# Equemetico.net
KiCad netlist of a schematic drawn in EAGLE
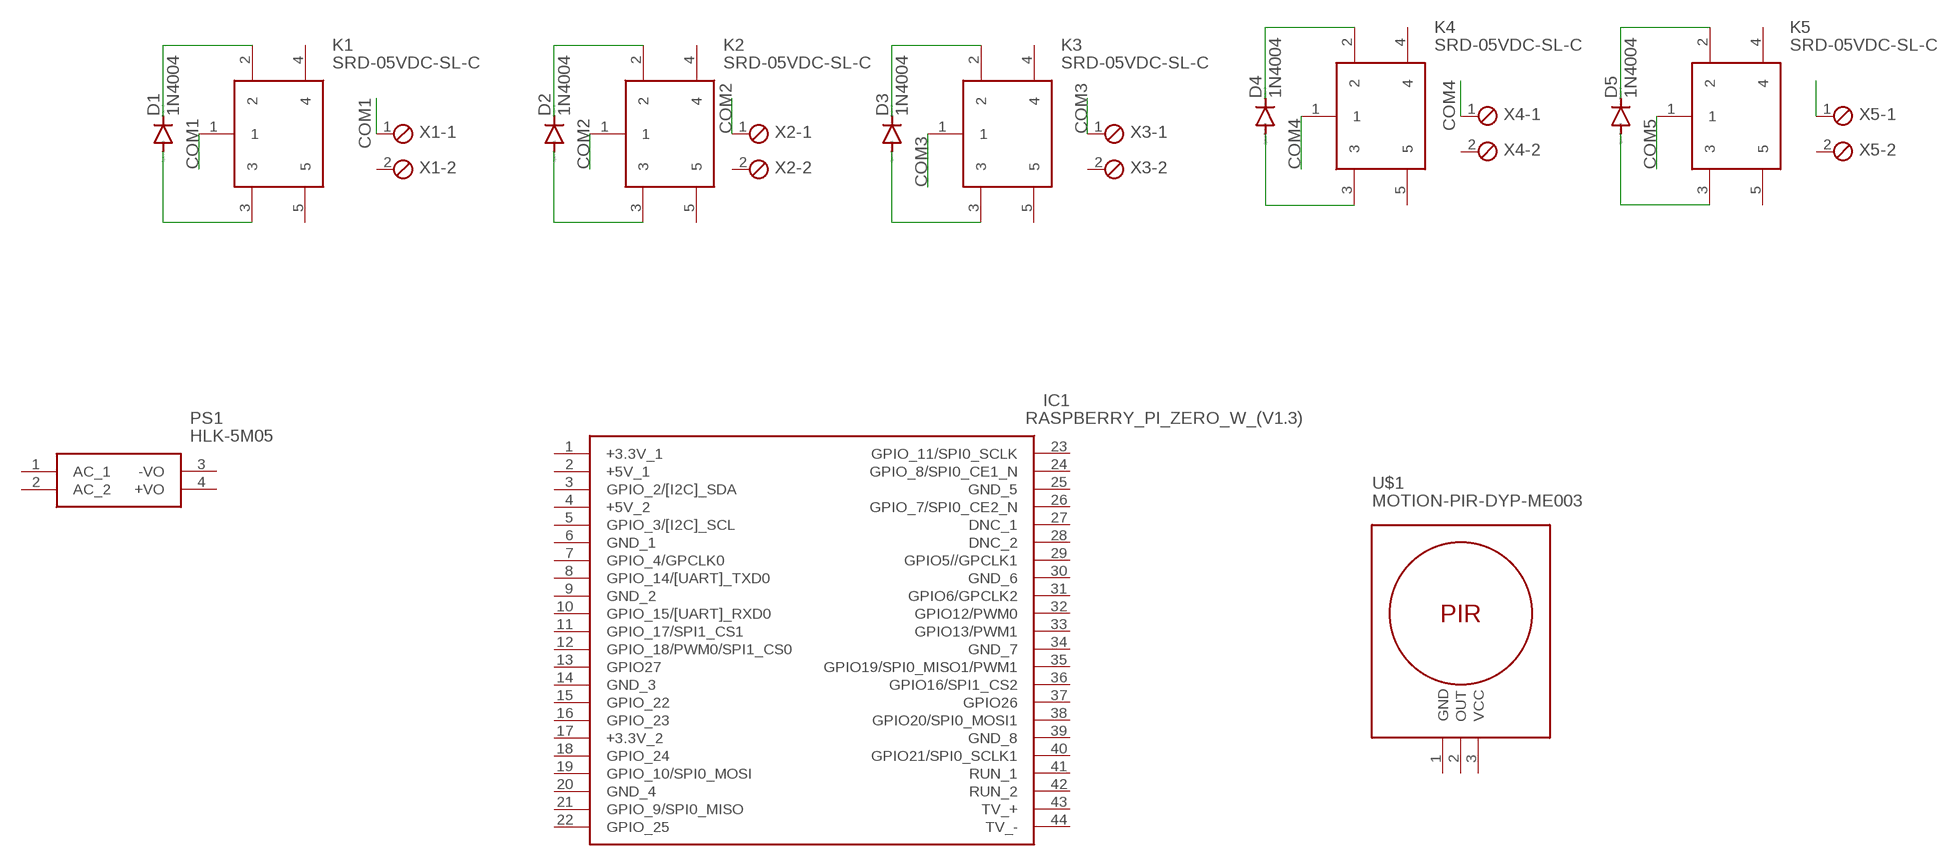
[diagram p0: schematic, sheet 1]

(export (version "E")
  (design (tool "Eeschema 10.0.6"))
  (components
    (comp (ref "D1")
      (value "1N4004")
      (footprint "eagle-import:DO41-10")
      (libsource (lib "eagle-import") (part "1N4004"))
    )
    (comp (ref "D2")
      (value "1N4004")
      (footprint "eagle-import:DO41-10")
      (libsource (lib "eagle-import") (part "1N4004"))
    )
    (comp (ref "D3")
      (value "1N4004")
      (footprint "eagle-import:DO41-10")
      (libsource (lib "eagle-import") (part "1N4004"))
    )
    (comp (ref "D4")
      (value "1N4004")
      (footprint "eagle-import:DO41-10")
      (libsource (lib "eagle-import") (part "1N4004"))
    )
    (comp (ref "D5")
      (value "1N4004")
      (footprint "eagle-import:DO41-10")
      (libsource (lib "eagle-import") (part "1N4004"))
    )
    (comp (ref "IC1")
      (value "RASPBERRY_PI_ZERO_W_(V1.3)")
      (footprint "eagle-import:RASPBERRYPIZEROWV13")
      (fields (field (name "MANUFACTURER_PART_NUMBER") "Raspberry Pi Zero W (v1.3)"))
      (libsource (lib "eagle-import") (part "RASPBERRY_PI_ZERO_W_(V1.3)"))
    )
    (comp (ref "K1")
      (value "SRD-05VDC-SL-C")
      (footprint "eagle-import:SRD")
      (libsource (lib "eagle-import") (part "SRD-05VDC-SL-C"))
    )
    (comp (ref "K2")
      (value "SRD-05VDC-SL-C")
      (footprint "eagle-import:SRD")
      (libsource (lib "eagle-import") (part "SRD-05VDC-SL-C"))
    )
    (comp (ref "K3")
      (value "SRD-05VDC-SL-C")
      (footprint "eagle-import:SRD")
      (libsource (lib "eagle-import") (part "SRD-05VDC-SL-C"))
    )
    (comp (ref "K4")
      (value "SRD-05VDC-SL-C")
      (footprint "eagle-import:SRD")
      (libsource (lib "eagle-import") (part "SRD-05VDC-SL-C"))
    )
    (comp (ref "K5")
      (value "SRD-05VDC-SL-C")
      (footprint "eagle-import:SRD")
      (libsource (lib "eagle-import") (part "SRD-05VDC-SL-C"))
    )
    (comp (ref "PS1")
      (value "HLK-5M05")
      (footprint "eagle-import:HLK5M05")
      (libsource (lib "eagle-import") (part "HLK-5M05"))
    )
    (comp (ref "U$1")
      (value "MOTION-PIR-DYP-ME003")
      (footprint "eagle-import:MOTION-PIR-DYP-ME003")
      (libsource (lib "eagle-import") (part "MOTION-PIR-DYP-ME003"))
    )
    (comp (ref "X1")
      (value "MPT2")
      (footprint "eagle-import:2POL254")
      (libsource (lib "eagle-import") (part "MPT2"))
    )
    (comp (ref "X2")
      (value "MPT2")
      (footprint "eagle-import:2POL254")
      (libsource (lib "eagle-import") (part "MPT2"))
    )
    (comp (ref "X3")
      (value "MPT2")
      (footprint "eagle-import:2POL254")
      (libsource (lib "eagle-import") (part "MPT2"))
    )
    (comp (ref "X4")
      (value "MPT2")
      (footprint "eagle-import:2POL254")
      (libsource (lib "eagle-import") (part "MPT2"))
    )
    (comp (ref "X5")
      (value "MPT2")
      (footprint "eagle-import:2POL254")
      (libsource (lib "eagle-import") (part "MPT2"))
    )
  )
  (nets
    (net (code "1") (name "/COM1") (class "Default")
      (node (ref "K1") (pin "1") (pinfunction "1_1") (pintype "bidirectional"))
      (node (ref "X1") (pin "1") (pinfunction "1_1") (pintype "passive"))
    )
    (net (code "2") (name "/COM2") (class "Default")
      (node (ref "K2") (pin "1") (pinfunction "1_1") (pintype "bidirectional"))
      (node (ref "X2") (pin "1") (pinfunction "1_1") (pintype "passive"))
    )
    (net (code "3") (name "/COM3") (class "Default")
      (node (ref "K3") (pin "1") (pinfunction "1_1") (pintype "bidirectional"))
      (node (ref "X3") (pin "1") (pinfunction "1_1") (pintype "passive"))
    )
    (net (code "4") (name "/COM4") (class "Default")
      (node (ref "K4") (pin "1") (pinfunction "1_1") (pintype "bidirectional"))
      (node (ref "X4") (pin "1") (pinfunction "1_1") (pintype "passive"))
    )
    (net (code "5") (name "/COM5") (class "Default")
      (node (ref "K5") (pin "1") (pinfunction "1_1") (pintype "bidirectional"))
      (node (ref "X5") (pin "1") (pinfunction "1_1") (pintype "passive"))
    )
    (net (code "6") (name "/GND") (class "Default")
      (node (ref "U$1") (pin "1") (pinfunction "GND_1") (pintype "power_in"))
    )
    (net (code "7") (name "/VCC") (class "Default")
      (node (ref "U$1") (pin "3") (pinfunction "VCC_3") (pintype "power_in"))
    )
    (net (code "8") (name "Net-(D1-PadA)") (class "Default")
      (node (ref "D1") (pin "A") (pinfunction "A_A") (pintype "passive"))
      (node (ref "K1") (pin "3") (pinfunction "3_3") (pintype "bidirectional"))
    )
    (net (code "9") (name "Net-(D1-PadC)") (class "Default")
      (node (ref "D1") (pin "C") (pinfunction "C_C") (pintype "passive"))
      (node (ref "K1") (pin "2") (pinfunction "2_2") (pintype "bidirectional"))
    )
    (net (code "10") (name "Net-(D2-PadA)") (class "Default")
      (node (ref "D2") (pin "A") (pinfunction "A_A") (pintype "passive"))
      (node (ref "K2") (pin "3") (pinfunction "3_3") (pintype "bidirectional"))
    )
    (net (code "11") (name "Net-(D2-PadC)") (class "Default")
      (node (ref "D2") (pin "C") (pinfunction "C_C") (pintype "passive"))
      (node (ref "K2") (pin "2") (pinfunction "2_2") (pintype "bidirectional"))
    )
    (net (code "12") (name "Net-(D3-PadA)") (class "Default")
      (node (ref "D3") (pin "A") (pinfunction "A_A") (pintype "passive"))
      (node (ref "K3") (pin "3") (pinfunction "3_3") (pintype "bidirectional"))
    )
    (net (code "13") (name "Net-(D3-PadC)") (class "Default")
      (node (ref "D3") (pin "C") (pinfunction "C_C") (pintype "passive"))
      (node (ref "K3") (pin "2") (pinfunction "2_2") (pintype "bidirectional"))
    )
    (net (code "14") (name "Net-(D4-PadA)") (class "Default")
      (node (ref "D4") (pin "A") (pinfunction "A_A") (pintype "passive"))
      (node (ref "K4") (pin "3") (pinfunction "3_3") (pintype "bidirectional"))
    )
    (net (code "15") (name "Net-(D4-PadC)") (class "Default")
      (node (ref "D4") (pin "C") (pinfunction "C_C") (pintype "passive"))
      (node (ref "K4") (pin "2") (pinfunction "2_2") (pintype "bidirectional"))
    )
    (net (code "16") (name "Net-(D5-PadA)") (class "Default")
      (node (ref "D5") (pin "A") (pinfunction "A_A") (pintype "passive"))
      (node (ref "K5") (pin "3") (pinfunction "3_3") (pintype "bidirectional"))
    )
    (net (code "17") (name "Net-(D5-PadC)") (class "Default")
      (node (ref "D5") (pin "C") (pinfunction "C_C") (pintype "passive"))
      (node (ref "K5") (pin "2") (pinfunction "2_2") (pintype "bidirectional"))
    )
    (net (code "18") (name "unconnected-(IC1-+3.3V_1-Pad1)") (class "Default")
      (node (ref "IC1") (pin "1") (pinfunction "+3.3V_1_1") (pintype "bidirectional"))
    )
    (net (code "19") (name "unconnected-(IC1-+3.3V_2-Pad17)") (class "Default")
      (node (ref "IC1") (pin "17") (pinfunction "+3.3V_2_17") (pintype "bidirectional"))
    )
    (net (code "20") (name "unconnected-(IC1-+5V_1-Pad2)") (class "Default")
      (node (ref "IC1") (pin "2") (pinfunction "+5V_1_2") (pintype "bidirectional"))
    )
    (net (code "21") (name "unconnected-(IC1-+5V_2-Pad4)") (class "Default")
      (node (ref "IC1") (pin "4") (pinfunction "+5V_2_4") (pintype "bidirectional"))
    )
    (net (code "22") (name "unconnected-(IC1-DNC_1-Pad27)") (class "Default")
      (node (ref "IC1") (pin "27") (pinfunction "DNC_1_27") (pintype "bidirectional"))
    )
    (net (code "23") (name "unconnected-(IC1-DNC_2-Pad28)") (class "Default")
      (node (ref "IC1") (pin "28") (pinfunction "DNC_2_28") (pintype "bidirectional"))
    )
    (net (code "24") (name "unconnected-(IC1-GND_1-Pad6)") (class "Default")
      (node (ref "IC1") (pin "6") (pinfunction "GND_1_6") (pintype "bidirectional"))
    )
    (net (code "25") (name "unconnected-(IC1-GND_2-Pad9)") (class "Default")
      (node (ref "IC1") (pin "9") (pinfunction "GND_2_9") (pintype "bidirectional"))
    )
    (net (code "26") (name "unconnected-(IC1-GND_3-Pad14)") (class "Default")
      (node (ref "IC1") (pin "14") (pinfunction "GND_3_14") (pintype "bidirectional"))
    )
    (net (code "27") (name "unconnected-(IC1-GND_4-Pad20)") (class "Default")
      (node (ref "IC1") (pin "20") (pinfunction "GND_4_20") (pintype "bidirectional"))
    )
    (net (code "28") (name "unconnected-(IC1-GND_5-Pad25)") (class "Default")
      (node (ref "IC1") (pin "25") (pinfunction "GND_5_25") (pintype "bidirectional"))
    )
    (net (code "29") (name "unconnected-(IC1-GND_6-Pad30)") (class "Default")
      (node (ref "IC1") (pin "30") (pinfunction "GND_6_30") (pintype "bidirectional"))
    )
    (net (code "30") (name "unconnected-(IC1-GND_7-Pad34)") (class "Default")
      (node (ref "IC1") (pin "34") (pinfunction "GND_7_34") (pintype "bidirectional"))
    )
    (net (code "31") (name "unconnected-(IC1-GND_8-Pad39)") (class "Default")
      (node (ref "IC1") (pin "39") (pinfunction "GND_8_39") (pintype "bidirectional"))
    )
    (net (code "32") (name "unconnected-(IC1-GPIO5{slash}{slash}GPCLK1-Pad29)") (class "Default")
      (node (ref "IC1") (pin "29") (pinfunction "GPIO5//GPCLK1_29") (pintype "bidirectional"))
    )
    (net (code "33") (name "unconnected-(IC1-GPIO6{slash}GPCLK2-Pad31)") (class "Default")
      (node (ref "IC1") (pin "31") (pinfunction "GPIO6/GPCLK2_31") (pintype "bidirectional"))
    )
    (net (code "34") (name "unconnected-(IC1-GPIO12{slash}PWM0-Pad32)") (class "Default")
      (node (ref "IC1") (pin "32") (pinfunction "GPIO12/PWM0_32") (pintype "bidirectional"))
    )
    (net (code "35") (name "unconnected-(IC1-GPIO13{slash}PWM1-Pad33)") (class "Default")
      (node (ref "IC1") (pin "33") (pinfunction "GPIO13/PWM1_33") (pintype "bidirectional"))
    )
    (net (code "36") (name "unconnected-(IC1-GPIO16{slash}SPI1_CS2-Pad36)") (class "Default")
      (node (ref "IC1") (pin "36") (pinfunction "GPIO16/SPI1_CS2_36") (pintype "bidirectional"))
    )
    (net (code "37") (name "unconnected-(IC1-GPIO19{slash}SPI0_MISO1{slash}PWM1-Pad35)") (class "Default")
      (node (ref "IC1") (pin "35") (pinfunction "GPIO19/SPI0_MISO1/PWM1_35") (pintype "bidirectional"))
    )
    (net (code "38") (name "unconnected-(IC1-GPIO20{slash}SPI0_MOSI1-Pad38)") (class "Default")
      (node (ref "IC1") (pin "38") (pinfunction "GPIO20/SPI0_MOSI1_38") (pintype "bidirectional"))
    )
    (net (code "39") (name "unconnected-(IC1-GPIO21{slash}SPI0_SCLK1-Pad40)") (class "Default")
      (node (ref "IC1") (pin "40") (pinfunction "GPIO21/SPI0_SCLK1_40") (pintype "bidirectional"))
    )
    (net (code "40") (name "unconnected-(IC1-GPIO26-Pad37)") (class "Default")
      (node (ref "IC1") (pin "37") (pinfunction "GPIO26_37") (pintype "bidirectional"))
    )
    (net (code "41") (name "unconnected-(IC1-GPIO27-Pad13)") (class "Default")
      (node (ref "IC1") (pin "13") (pinfunction "GPIO27_13") (pintype "bidirectional"))
    )
    (net (code "42") (name "unconnected-(IC1-GPIO_2{slash}[I2C]_SDA-Pad3)") (class "Default")
      (node (ref "IC1") (pin "3") (pinfunction "GPIO_2/[I2C]_SDA_3") (pintype "bidirectional"))
    )
    (net (code "43") (name "unconnected-(IC1-GPIO_3{slash}[I2C]_SCL-Pad5)") (class "Default")
      (node (ref "IC1") (pin "5") (pinfunction "GPIO_3/[I2C]_SCL_5") (pintype "bidirectional"))
    )
    (net (code "44") (name "unconnected-(IC1-GPIO_4{slash}GPCLK0-Pad7)") (class "Default")
      (node (ref "IC1") (pin "7") (pinfunction "GPIO_4/GPCLK0_7") (pintype "bidirectional"))
    )
    (net (code "45") (name "unconnected-(IC1-GPIO_7{slash}SPI0_CE2_N-Pad26)") (class "Default")
      (node (ref "IC1") (pin "26") (pinfunction "GPIO_7/SPI0_CE2_N_26") (pintype "bidirectional"))
    )
    (net (code "46") (name "unconnected-(IC1-GPIO_8{slash}SPI0_CE1_N-Pad24)") (class "Default")
      (node (ref "IC1") (pin "24") (pinfunction "GPIO_8/SPI0_CE1_N_24") (pintype "bidirectional"))
    )
    (net (code "47") (name "unconnected-(IC1-GPIO_9{slash}SPI0_MISO-Pad21)") (class "Default")
      (node (ref "IC1") (pin "21") (pinfunction "GPIO_9/SPI0_MISO_21") (pintype "bidirectional"))
    )
    (net (code "48") (name "unconnected-(IC1-GPIO_10{slash}SPI0_MOSI-Pad19)") (class "Default")
      (node (ref "IC1") (pin "19") (pinfunction "GPIO_10/SPI0_MOSI_19") (pintype "bidirectional"))
    )
    (net (code "49") (name "unconnected-(IC1-GPIO_11{slash}SPI0_SCLK-Pad23)") (class "Default")
      (node (ref "IC1") (pin "23") (pinfunction "GPIO_11/SPI0_SCLK_23") (pintype "bidirectional"))
    )
    (net (code "50") (name "unconnected-(IC1-GPIO_14{slash}[UART]_TXD0-Pad8)") (class "Default")
      (node (ref "IC1") (pin "8") (pinfunction "GPIO_14/[UART]_TXD0_8") (pintype "bidirectional"))
    )
    (net (code "51") (name "unconnected-(IC1-GPIO_15{slash}[UART]_RXD0-Pad10)") (class "Default")
      (node (ref "IC1") (pin "10") (pinfunction "GPIO_15/[UART]_RXD0_10") (pintype "bidirectional"))
    )
    (net (code "52") (name "unconnected-(IC1-GPIO_17{slash}SPI1_CS1-Pad11)") (class "Default")
      (node (ref "IC1") (pin "11") (pinfunction "GPIO_17/SPI1_CS1_11") (pintype "bidirectional"))
    )
    (net (code "53") (name "unconnected-(IC1-GPIO_18{slash}PWM0{slash}SPI1_CS0-Pad12)") (class "Default")
      (node (ref "IC1") (pin "12") (pinfunction "GPIO_18/PWM0/SPI1_CS0_12") (pintype "bidirectional"))
    )
    (net (code "54") (name "unconnected-(IC1-GPIO_22-Pad15)") (class "Default")
      (node (ref "IC1") (pin "15") (pinfunction "GPIO_22_15") (pintype "bidirectional"))
    )
    (net (code "55") (name "unconnected-(IC1-GPIO_23-Pad16)") (class "Default")
      (node (ref "IC1") (pin "16") (pinfunction "GPIO_23_16") (pintype "bidirectional"))
    )
    (net (code "56") (name "unconnected-(IC1-GPIO_24-Pad18)") (class "Default")
      (node (ref "IC1") (pin "18") (pinfunction "GPIO_24_18") (pintype "bidirectional"))
    )
    (net (code "57") (name "unconnected-(IC1-GPIO_25-Pad22)") (class "Default")
      (node (ref "IC1") (pin "22") (pinfunction "GPIO_25_22") (pintype "bidirectional"))
    )
    (net (code "58") (name "unconnected-(IC1-RUN_1-Pad41)") (class "Default")
      (node (ref "IC1") (pin "41") (pinfunction "RUN_1_41") (pintype "bidirectional"))
    )
    (net (code "59") (name "unconnected-(IC1-RUN_2-Pad42)") (class "Default")
      (node (ref "IC1") (pin "42") (pinfunction "RUN_2_42") (pintype "bidirectional"))
    )
    (net (code "60") (name "unconnected-(IC1-TV_+-Pad43)") (class "Default")
      (node (ref "IC1") (pin "43") (pinfunction "TV_+_43") (pintype "bidirectional"))
    )
    (net (code "61") (name "unconnected-(IC1-TV_--Pad44)") (class "Default")
      (node (ref "IC1") (pin "44") (pinfunction "TV_-_44") (pintype "bidirectional"))
    )
    (net (code "62") (name "unconnected-(K1-Pad4)") (class "Default")
      (node (ref "K1") (pin "4") (pinfunction "4_4") (pintype "bidirectional"))
    )
    (net (code "63") (name "unconnected-(K1-Pad5)") (class "Default")
      (node (ref "K1") (pin "5") (pinfunction "5_5") (pintype "bidirectional"))
    )
    (net (code "64") (name "unconnected-(K2-Pad4)") (class "Default")
      (node (ref "K2") (pin "4") (pinfunction "4_4") (pintype "bidirectional"))
    )
    (net (code "65") (name "unconnected-(K2-Pad5)") (class "Default")
      (node (ref "K2") (pin "5") (pinfunction "5_5") (pintype "bidirectional"))
    )
    (net (code "66") (name "unconnected-(K3-Pad4)") (class "Default")
      (node (ref "K3") (pin "4") (pinfunction "4_4") (pintype "bidirectional"))
    )
    (net (code "67") (name "unconnected-(K3-Pad5)") (class "Default")
      (node (ref "K3") (pin "5") (pinfunction "5_5") (pintype "bidirectional"))
    )
    (net (code "68") (name "unconnected-(K4-Pad4)") (class "Default")
      (node (ref "K4") (pin "4") (pinfunction "4_4") (pintype "bidirectional"))
    )
    (net (code "69") (name "unconnected-(K4-Pad5)") (class "Default")
      (node (ref "K4") (pin "5") (pinfunction "5_5") (pintype "bidirectional"))
    )
    (net (code "70") (name "unconnected-(K5-Pad4)") (class "Default")
      (node (ref "K5") (pin "4") (pinfunction "4_4") (pintype "bidirectional"))
    )
    (net (code "71") (name "unconnected-(K5-Pad5)") (class "Default")
      (node (ref "K5") (pin "5") (pinfunction "5_5") (pintype "bidirectional"))
    )
    (net (code "72") (name "unconnected-(PS1-+VO-Pad4)") (class "Default")
      (node (ref "PS1") (pin "4") (pinfunction "+VO_4") (pintype "bidirectional"))
    )
    (net (code "73") (name "unconnected-(PS1--VO-Pad3)") (class "Default")
      (node (ref "PS1") (pin "3") (pinfunction "-VO_3") (pintype "bidirectional"))
    )
    (net (code "74") (name "unconnected-(PS1-AC_1-Pad1)") (class "Default")
      (node (ref "PS1") (pin "1") (pinfunction "AC_1_1") (pintype "bidirectional"))
    )
    (net (code "75") (name "unconnected-(PS1-AC_2-Pad2)") (class "Default")
      (node (ref "PS1") (pin "2") (pinfunction "AC_2_2") (pintype "bidirectional"))
    )
    (net (code "76") (name "unconnected-(U$1-OUT-Pad2)") (class "Default")
      (node (ref "U$1") (pin "2") (pinfunction "OUT_2") (pintype "output"))
    )
    (net (code "77") (name "unconnected-(X1B-1-Pad2)") (class "Default")
      (node (ref "X1") (pin "2") (pinfunction "1_2") (pintype "passive"))
    )
    (net (code "78") (name "unconnected-(X2B-1-Pad2)") (class "Default")
      (node (ref "X2") (pin "2") (pinfunction "1_2") (pintype "passive"))
    )
    (net (code "79") (name "unconnected-(X3B-1-Pad2)") (class "Default")
      (node (ref "X3") (pin "2") (pinfunction "1_2") (pintype "passive"))
    )
    (net (code "80") (name "unconnected-(X4B-1-Pad2)") (class "Default")
      (node (ref "X4") (pin "2") (pinfunction "1_2") (pintype "passive"))
    )
    (net (code "81") (name "unconnected-(X5B-1-Pad2)") (class "Default")
      (node (ref "X5") (pin "2") (pinfunction "1_2") (pintype "passive"))
    )
  )
)
